# Schematic_of_device.net
KiCad netlist of a schematic drawn in Altium Designer
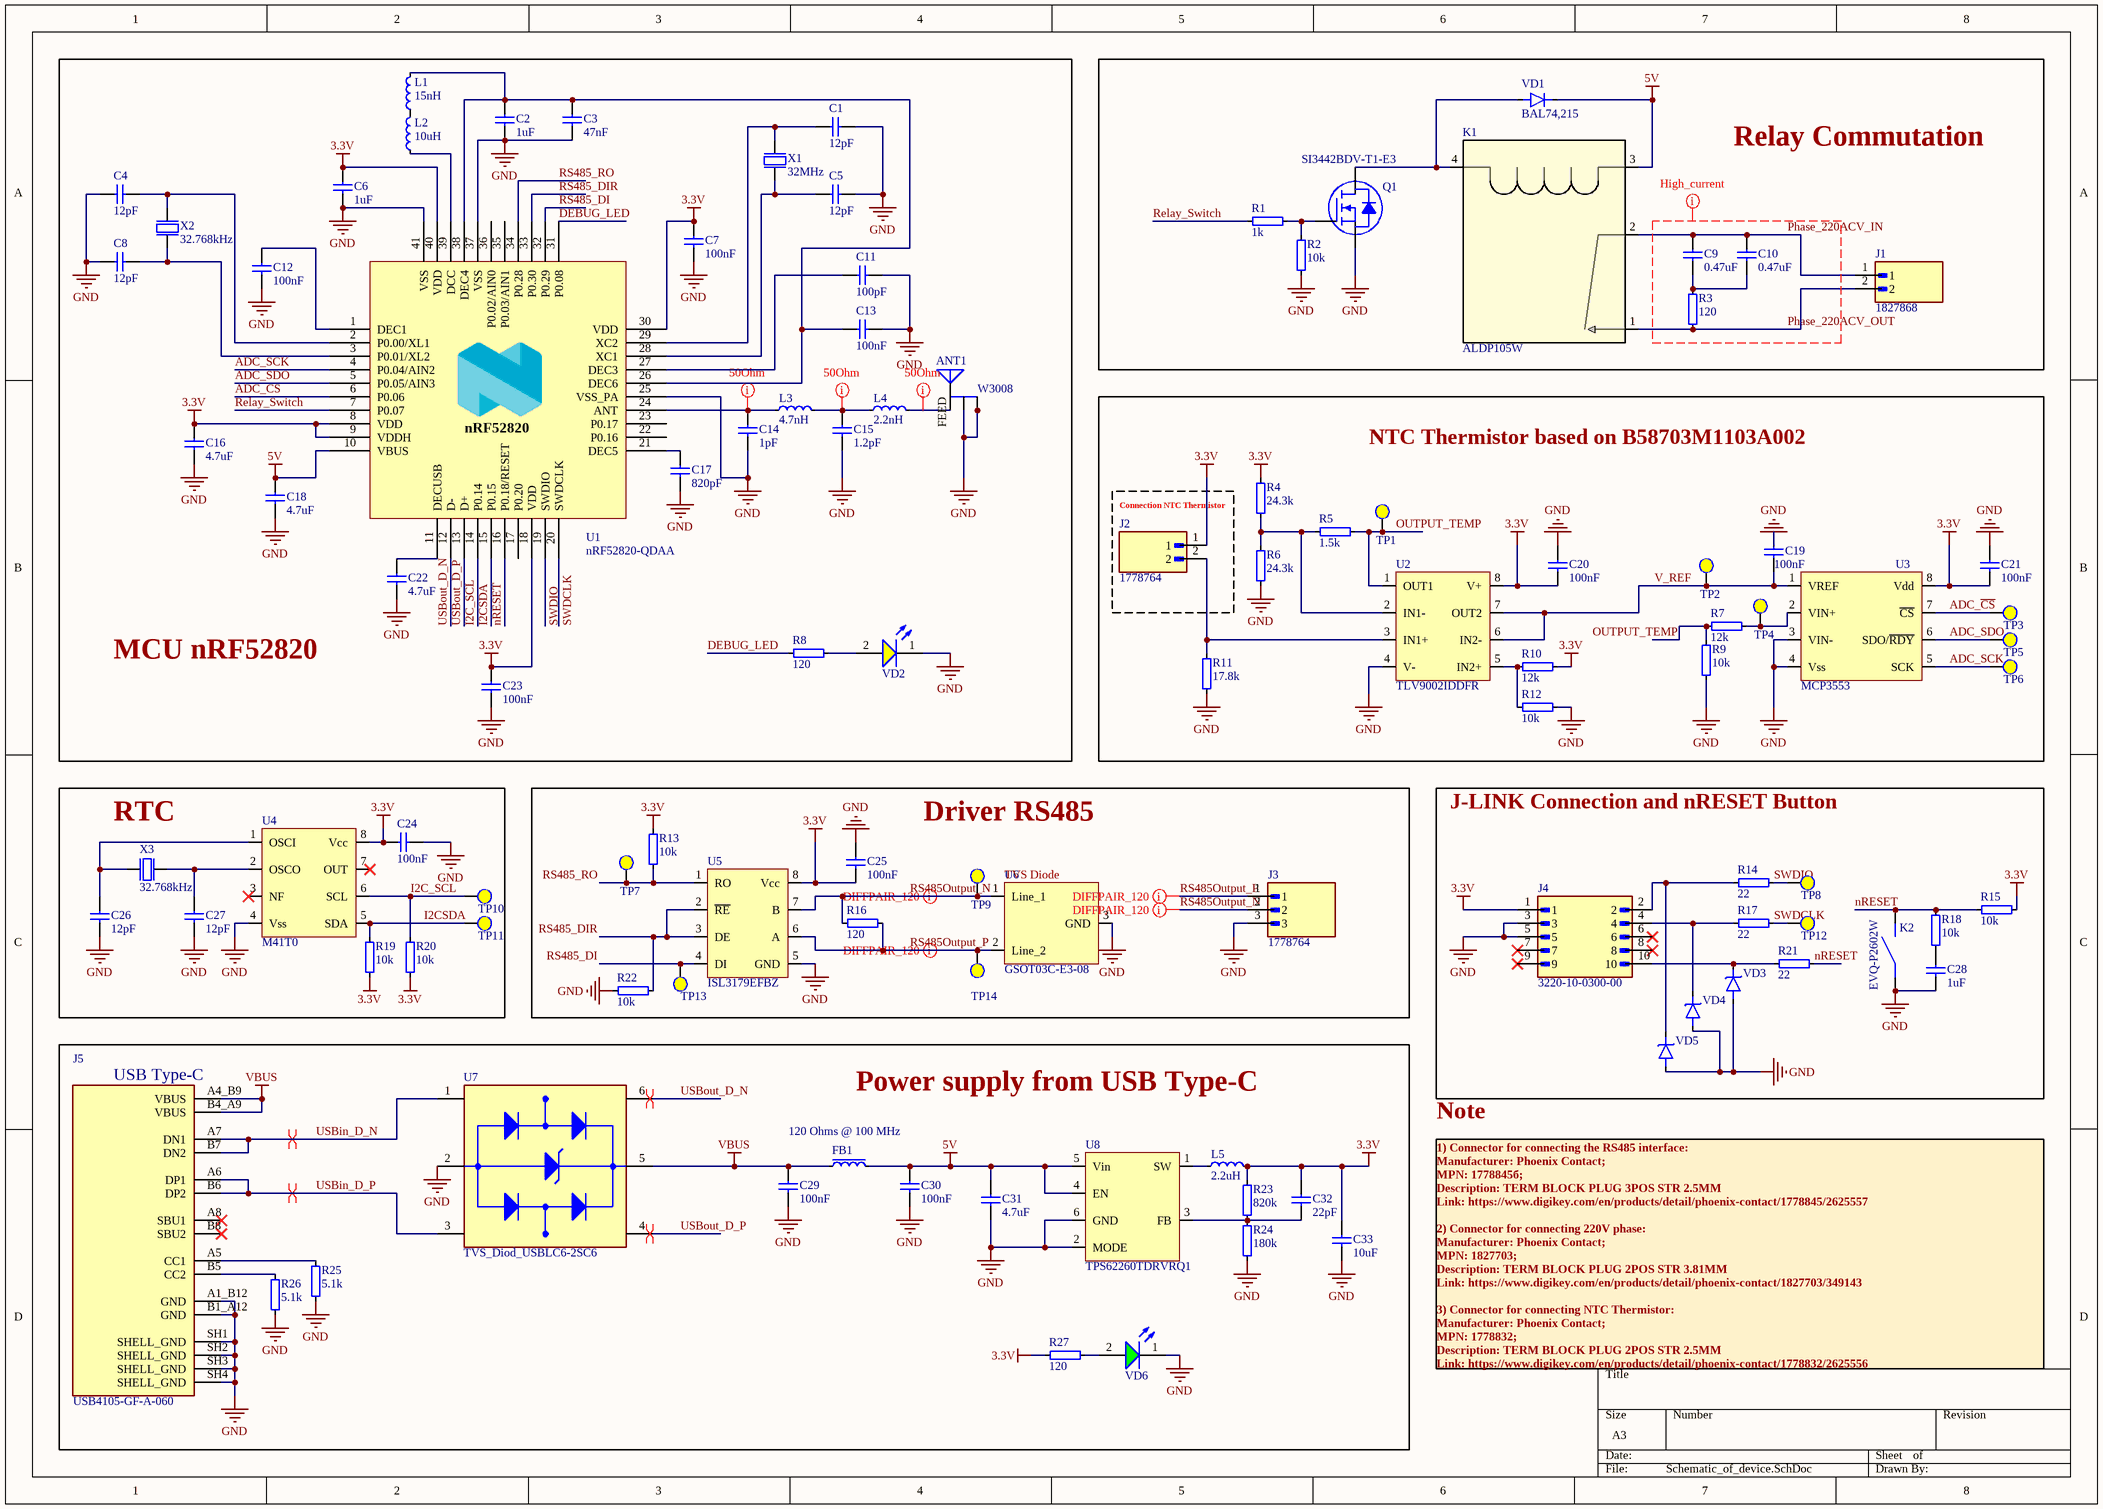
[diagram p0: Schematic_of_device.SchDoc]

(export (version "E")
  (design (tool "Eeschema 10.0.6"))
  (components
    (comp (ref "ANT1")
      (value "W3008")
      (footprint "3")
      (description "2.4GHz Bluetooth, WLAN, Zigbeeâ„¢ Chip RF Antenna 2.4GHz ~ 2.483GHz 2.2dBi Solder Surface Mount")
      (fields (field (name "MF") "PulseLarsen Antennas"))
      (libsource (lib "TT_lib") (part "W3008"))
    )
    (comp (ref "C1")
      (value "12pF")
      (footprint "C_Chip_0402")
      (description "CAP CER 12PF 200V NP0 0402")
      (fields (field (name "MANUFACTURER") "Murata Electronics") (field (name "MPN") "GQM1555C2D120FB01D"))
      (libsource (lib "TT_lib") (part "С_Chip_0402_12p"))
    )
    (comp (ref "C2")
      (value "1uF")
      (footprint "C_Chip_0402")
      (description "CAP CER 1UF 10V X7R 0402")
      (fields (field (name "MANUFACTURER") "Murata Electronics") (field (name "MPN") "GRM155Z71A105KE01J"))
      (libsource (lib "TT_lib") (part "С_Chip_0402_1u"))
    )
    (comp (ref "C3")
      (value "47nF")
      (footprint "C_Chip_0402")
      (description "CAP CER 0.047UF 50V X7R 0402")
      (fields (field (name "MANUFACTURER") "Murata Electronics") (field (name "MPN") "GRM155R71H473KE14D"))
      (libsource (lib "TT_lib") (part "С_Chip_0402_47n"))
    )
    (comp (ref "C4")
      (value "12pF")
      (footprint "C_Chip_0402")
      (description "CAP CER 12PF 200V NP0 0402")
      (fields (field (name "MANUFACTURER") "Murata Electronics") (field (name "MPN") "GQM1555C2D120FB01D"))
      (libsource (lib "TT_lib") (part "С_Chip_0402_12p"))
    )
    (comp (ref "C5")
      (value "12pF")
      (footprint "C_Chip_0402")
      (description "CAP CER 12PF 200V NP0 0402")
      (fields (field (name "MANUFACTURER") "Murata Electronics") (field (name "MPN") "GQM1555C2D120FB01D"))
      (libsource (lib "TT_lib") (part "С_Chip_0402_12p"))
    )
    (comp (ref "C6")
      (value "1uF")
      (footprint "C_Chip_0402")
      (description "CAP CER 1UF 10V X7R 0402")
      (fields (field (name "MANUFACTURER") "Murata Electronics") (field (name "MPN") "GRM155Z71A105KE01J"))
      (libsource (lib "TT_lib") (part "С_Chip_0402_1u"))
    )
    (comp (ref "C7")
      (value "100nF")
      (footprint "C_Chip_0402")
      (description "CAP CER 0.1UF 50V X7R 0402")
      (fields (field (name "MANUFACTURER") "Murata Electronics") (field (name "MPN") "GCM155R71H104KE02D"))
      (libsource (lib "TT_lib") (part "С_Chip_0402_100n"))
    )
    (comp (ref "C8")
      (value "12pF")
      (footprint "C_Chip_0402")
      (description "CAP CER 12PF 200V NP0 0402")
      (fields (field (name "MANUFACTURER") "Murata Electronics") (field (name "MPN") "GQM1555C2D120FB01D"))
      (libsource (lib "TT_lib") (part "С_Chip_0402_12p"))
    )
    (comp (ref "C9")
      (value "0.47uF")
      (footprint "C_Chip_1812")
      (description "CAP CER 0.47UF 500V X7R 1812")
      (fields
        (field (name "MANUFACTURER") "Holy Stone Enterprise Co., Ltd.")
        (field (name "MPN") "C1812X474K501T")
      )
      (libsource (lib "TT_lib") (part "С_Chip_1812_0u47"))
    )
    (comp (ref "C10")
      (value "0.47uF")
      (footprint "C_Chip_1812")
      (description "CAP CER 0.47UF 500V X7R 1812")
      (fields
        (field (name "MANUFACTURER") "Holy Stone Enterprise Co., Ltd.")
        (field (name "MPN") "C1812X474K501T")
      )
      (libsource (lib "TT_lib") (part "С_Chip_1812_0u47"))
    )
    (comp (ref "C11")
      (value "100pF")
      (footprint "C_Chip_0402")
      (description "CAP CER 100PF 50V X7R 0402")
      (fields (field (name "MANUFACTURER") "Würth Elektronik") (field (name "MPN") "885012205055"))
      (libsource (lib "TT_lib") (part "С_Chip_0402_100p"))
    )
    (comp (ref "C12")
      (value "100nF")
      (footprint "C_Chip_0402")
      (description "CAP CER 0.1UF 50V X7R 0402")
      (fields (field (name "MANUFACTURER") "Murata Electronics") (field (name "MPN") "GCM155R71H104KE02D"))
      (libsource (lib "TT_lib") (part "С_Chip_0402_100n"))
    )
    (comp (ref "C13")
      (value "100nF")
      (footprint "C_Chip_0402")
      (description "CAP CER 0.1UF 50V X7R 0402")
      (fields (field (name "MANUFACTURER") "Murata Electronics") (field (name "MPN") "GCM155R71H104KE02D"))
      (libsource (lib "TT_lib") (part "С_Chip_0402_100n"))
    )
    (comp (ref "C14")
      (value "1pF")
      (footprint "C_Chip_0402")
      (description "CAP CER 1PF 50V C0G/NP0 0402")
      (fields (field (name "MANUFACTURER") "Murata Electronics") (field (name "MPN") "GJM1555C1H1R0WB01D"))
      (libsource (lib "TT_lib") (part "С_Chip_0402_1p"))
    )
    (comp (ref "C15")
      (value "1.2pF")
      (footprint "C_Chip_0402")
      (description "CAP CER 1.2PF 50V C0G/NP0 0402")
      (fields (field (name "MANUFACTURER") "Murata Electronics") (field (name "MPN") "GRM1555C1H1R2BA01D"))
      (libsource (lib "TT_lib") (part "С_Chip_0402_1p2"))
    )
    (comp (ref "C16")
      (value "4.7uF")
      (footprint "C_Chip_0402")
      (description "CAP CER 4.7UF 16V X6T 0402")
      (fields (field (name "MANUFACTURER") "Murata Electronics") (field (name "MPN") "GRM155D81C475ME15J"))
      (libsource (lib "TT_lib") (part "С_Chip_0402_4u7"))
    )
    (comp (ref "C17")
      (value "820pF")
      (footprint "C_Chip_0402")
      (description "CAP CER 820PF 50V X7R 0402")
      (fields (field (name "MANUFACTURER") "Murata Electronics") (field (name "MPN") "GRM155R71H821KA01D"))
      (libsource (lib "TT_lib") (part "С_Chip_0402_820p"))
    )
    (comp (ref "C18")
      (value "4.7uF")
      (footprint "C_Chip_0402")
      (description "CAP CER 4.7UF 16V X6T 0402")
      (fields (field (name "MANUFACTURER") "Murata Electronics") (field (name "MPN") "GRM155D81C475ME15J"))
      (libsource (lib "TT_lib") (part "С_Chip_0402_4u7"))
    )
    (comp (ref "C19")
      (value "100nF")
      (footprint "C_Chip_0402")
      (description "CAP CER 0.1UF 50V X7R 0402")
      (fields (field (name "MANUFACTURER") "Murata Electronics") (field (name "MPN") "GCM155R71H104KE02D"))
      (libsource (lib "TT_lib") (part "С_Chip_0402_100n"))
    )
    (comp (ref "C20")
      (value "100nF")
      (footprint "C_Chip_0402")
      (description "CAP CER 0.1UF 50V X7R 0402")
      (fields (field (name "MANUFACTURER") "Murata Electronics") (field (name "MPN") "GCM155R71H104KE02D"))
      (libsource (lib "TT_lib") (part "С_Chip_0402_100n"))
    )
    (comp (ref "C21")
      (value "100nF")
      (footprint "C_Chip_0402")
      (description "CAP CER 0.1UF 50V X7R 0402")
      (fields (field (name "MANUFACTURER") "Murata Electronics") (field (name "MPN") "GCM155R71H104KE02D"))
      (libsource (lib "TT_lib") (part "С_Chip_0402_100n"))
    )
    (comp (ref "C22")
      (value "4.7uF")
      (footprint "C_Chip_0402")
      (description "CAP CER 4.7UF 16V X6T 0402")
      (fields (field (name "MANUFACTURER") "Murata Electronics") (field (name "MPN") "GRM155D81C475ME15J"))
      (libsource (lib "TT_lib") (part "С_Chip_0402_4u7"))
    )
    (comp (ref "C23")
      (value "100nF")
      (footprint "C_Chip_0402")
      (description "CAP CER 0.1UF 50V X7R 0402")
      (fields (field (name "MANUFACTURER") "Murata Electronics") (field (name "MPN") "GCM155R71H104KE02D"))
      (libsource (lib "TT_lib") (part "С_Chip_0402_100n"))
    )
    (comp (ref "C24")
      (value "100nF")
      (footprint "C_Chip_0402")
      (description "CAP CER 0.1UF 50V X7R 0402")
      (fields (field (name "MANUFACTURER") "Murata Electronics") (field (name "MPN") "GCM155R71H104KE02D"))
      (libsource (lib "TT_lib") (part "С_Chip_0402_100n"))
    )
    (comp (ref "C25")
      (value "100nF")
      (footprint "C_Chip_0402")
      (description "CAP CER 0.1UF 50V X7R 0402")
      (fields (field (name "MANUFACTURER") "Murata Electronics") (field (name "MPN") "GCM155R71H104KE02D"))
      (libsource (lib "TT_lib") (part "С_Chip_0402_100n"))
    )
    (comp (ref "C26")
      (value "12pF")
      (footprint "C_Chip_0402")
      (description "CAP CER 12PF 200V NP0 0402")
      (fields (field (name "MANUFACTURER") "Murata Electronics") (field (name "MPN") "GQM1555C2D120FB01D"))
      (libsource (lib "TT_lib") (part "С_Chip_0402_12p"))
    )
    (comp (ref "C27")
      (value "12pF")
      (footprint "C_Chip_0402")
      (description "CAP CER 12PF 200V NP0 0402")
      (fields (field (name "MANUFACTURER") "Murata Electronics") (field (name "MPN") "GQM1555C2D120FB01D"))
      (libsource (lib "TT_lib") (part "С_Chip_0402_12p"))
    )
    (comp (ref "C28")
      (value "1uF")
      (footprint "C_Chip_0402")
      (description "CAP CER 1UF 10V X7R 0402")
      (fields (field (name "MANUFACTURER") "Murata Electronics") (field (name "MPN") "GRM155Z71A105KE01J"))
      (libsource (lib "TT_lib") (part "С_Chip_0402_1u"))
    )
    (comp (ref "C29")
      (value "100nF")
      (footprint "C_Chip_0402")
      (description "CAP CER 0.1UF 50V X7R 0402")
      (fields (field (name "MANUFACTURER") "Murata Electronics") (field (name "MPN") "GCM155R71H104KE02D"))
      (libsource (lib "TT_lib") (part "С_Chip_0402_100n"))
    )
    (comp (ref "C30")
      (value "100nF")
      (footprint "C_Chip_0402")
      (description "CAP CER 0.1UF 50V X7R 0402")
      (fields (field (name "MANUFACTURER") "Murata Electronics") (field (name "MPN") "GCM155R71H104KE02D"))
      (libsource (lib "TT_lib") (part "С_Chip_0402_100n"))
    )
    (comp (ref "C31")
      (value "4.7uF")
      (footprint "C_Chip_0603")
      (description "CAP CER 4.7UF 16V X7R 0603")
      (fields (field (name "MANUFACTURER") "Murata Electronics") (field (name "MPN") "GRM188Z71C475KE21D"))
      (libsource (lib "TT_lib") (part "С_Chip_0603_4u7"))
    )
    (comp (ref "C32")
      (value "22pF")
      (footprint "C_Chip_0402")
      (description "CAP CER 22PF 16V X7R 0402")
      (fields (field (name "MANUFACTURER") "KEMET") (field (name "MPN") "C0402C220K4RAC7867"))
      (libsource (lib "TT_lib") (part "С_Chip_0402_22p"))
    )
    (comp (ref "C33")
      (value "10uF")
      (footprint "C_Chip_0603")
      (description "CAP CER 10UF 10V X7R 0603")
      (fields (field (name "MANUFACTURER") "Murata Electronics") (field (name "MPN") "GRM188Z71A106MA73D"))
      (libsource (lib "TT_lib") (part "С_Chip_0603_10u"))
    )
    (comp (ref "FB1")
      (value "120 Ohms @ 100 MHz")
      (footprint "Ferrite_Bead_0402")
      (description "FERRITE BEAD 120 OHM 0402 1LN")
      (fields
        (field (name "MANUFACTURER") "Laird-Signal Integrity Products")
        (field (name "MPN") "LI0402D121R-10")
      )
      (libsource (lib "TT_lib") (part "Ferrite_Beads"))
    )
    (comp (ref "J1")
      (value "1827868")
      (footprint "Phoenix_1827868")
      (description "TERM BLOCK HDR 2POS 90DEG 3.81MM")
      (fields (field (name "MANUFACTURER") "Phoenix Contact"))
      (libsource (lib "TT_lib") (part "Phoenix_2pin_male"))
    )
    (comp (ref "J2")
      (value "1778764")
      (footprint "PHoenix_1778764")
      (description "TERM BLOCK HDR 2POS 90DEG 2.5MM")
      (fields (field (name "MANUFACTURER") "Phoenix Contact"))
      (libsource (lib "TT_lib") (part "Male_2_Position_Terminal_Block_Header"))
    )
    (comp (ref "J3")
      (value "1778764")
      (footprint "Phoenix_1778777")
      (description "TERM BLOCK HDR 3POS 90DEG 2.5MM")
      (fields (field (name "MANUFACTURER") "Phoenix Contact") (field (name "MPN") "1778777"))
      (libsource (lib "TT_lib") (part "Male_3_Position_Terminal_Block_Header"))
    )
    (comp (ref "J4")
      (value "3220-10-0300-00")
      (footprint "CNC_TECH_")
      (description "CONN HEADER SMD 10POS 1.27MM")
      (fields (field (name "MANUFACTURER") "CNC Tech"))
      (libsource (lib "TT_lib") (part "3220-10-0300-00"))
    )
    (comp (ref "J5")
      (value "USB4105-GF-A-060")
      (footprint "USB_TypeC_FP")
      (description "CONN RCP USB2.0 TYP C 24P SMD RA")
      (fields (field (name "MANUFACTURER") "GCT"))
      (libsource (lib "TT_lib") (part "USB_TypeC"))
    )
    (comp (ref "K1")
      (value "ALDP105W")
      (footprint "Rekay")
      (description "RELAY GEN PURPOSE SPST 5A 5V")
      (fields (field (name "MANUFACTURER") "Panasonic Electric Works"))
      (libsource (lib "TT_lib") (part "Relay"))
    )
    (comp (ref "K2")
      (value "EVQ-P2602W")
      (footprint "Button")
      (description "SWITCH TACTILE SPST-NO 0.02A 15V")
      (fields (field (name "MANUFACTURER") "Panasonic Electronic Components"))
      (libsource (lib "TT_lib") (part "Button"))
    )
    (comp (ref "L1")
      (value "15nH")
      (footprint "L_Chip_0402")
      (description "FIXED IND 15NH 250MA 600MOHM SMD")
      (fields
        (field (name "MANUFACTURER") "Johanson Technology Inc.")
        (field (name "MPN") "LRC0402CJ15NGV001T")
      )
      (libsource (lib "TT_lib") (part "L_Chip_0402_15n"))
    )
    (comp (ref "L2")
      (value "10uH")
      (footprint "L_Chip_0402")
      (description "FIXED IND 10UH 380MA 468MOHM SMD")
      (fields (field (name "MANUFACTURER") "Taiyo Yuden") (field (name "MPN") "CBMF1608T100K"))
      (libsource (lib "TT_lib") (part "L_Chip_0402_10u"))
    )
    (comp (ref "L3")
      (value "4.7nH")
      (footprint "L_Chip_0402")
      (description "FIXED IND 4.7NH 700MA 0.16OHM SM")
      (fields (field (name "MANUFACTURER") "Murata Electronics") (field (name "MPN") "LQG15HS4N7S02D"))
      (libsource (lib "TT_lib") (part "L_Chip_0402_4n7"))
    )
    (comp (ref "L4")
      (value "2.2nH")
      (footprint "L_Chip_0402")
      (description "FIXED IND 2.2NH 900MA 150MOHM SM")
      (fields (field (name "MANUFACTURER") "TDK Corporation") (field (name "MPN") "MLG1005S2N2BT000"))
      (libsource (lib "TT_lib") (part "L_Chip_0402_2n2"))
    )
    (comp (ref "L5")
      (value "2.2uH")
      (footprint "L_Chip_1008")
      (description "FIXED IND 2.2UH 1A 150 MOHM SMD")
      (fields (field (name "MANUFACTURER") "Murata Electronics") (field (name "MPN") "LQM2HPN2R2MJ0L"))
      (libsource (lib "TT_lib") (part "L_Chip_1008_2u2"))
    )
    (comp (ref "Q1")
      (value "SI3442BDV-T1-E3")
      (footprint "TSOP-6")
      (description "MOSFET N-CH 20V 3A 6TSOP")
      (fields (field (name "MANUFACTURER") "Vishay Siliconix"))
      (libsource (lib "TT_lib") (part "N-chenal_MOSFET"))
    )
    (comp (ref "R1")
      (value "1k")
      (footprint "R_Chip_0402")
      (description "RES 1K OHM 1% 1/8W 0402")
      (fields (field (name "MANUFACTURER") "YAGEO") (field (name "MPN") "AC0402FR-7W1KL"))
      (libsource (lib "TT_lib") (part "R_Chip_0402_1k"))
    )
    (comp (ref "R2")
      (value "10k")
      (footprint "R_Chip_0402")
      (description "RES 10K OHM 1% 1/8W 0402")
      (fields
        (field (name "MANUFACTURER") "TE Connectivity Passive Product")
        (field (name "MPN") "CRGP0402F10K")
      )
      (libsource (lib "TT_lib") (part "R_Chip_0402_10k"))
    )
    (comp (ref "R3")
      (value "120")
      (footprint "R_Chip_1210")
      (description "RES 120 OHM 1% 1W 1210")
      (fields (field (name "MANUFACTURER") "YAGEO") (field (name "MPN") "AC1210FR-7W120RL"))
      (libsource (lib "TT_lib") (part "R_Chip_1210_120"))
    )
    (comp (ref "R4")
      (value "24.3k")
      (footprint "R_Chip_0402")
      (description "RES 24.3K OHM 1% 1/8W 0402")
      (fields (field (name "MANUFACTURER") "YAGEO") (field (name "MPN") "AC0402FR-7W24K3L"))
      (libsource (lib "TT_lib") (part "R_Chip_0402_24k3"))
    )
    (comp (ref "R5")
      (value "1.5k")
      (footprint "R_Chip_0402")
      (description "RES 1.5K OHM 1% 1/8W 0402")
      (fields
        (field (name "MANUFACTURER") "TE Connectivity Passive Product")
        (field (name "MPN") "CRGP0402F1K5")
      )
      (libsource (lib "TT_lib") (part "R_Chip_0402_1k5"))
    )
    (comp (ref "R6")
      (value "24.3k")
      (footprint "R_Chip_0402")
      (description "RES 24.3K OHM 1% 1/8W 0402")
      (fields (field (name "MANUFACTURER") "YAGEO") (field (name "MPN") "AC0402FR-7W24K3L"))
      (libsource (lib "TT_lib") (part "R_Chip_0402_24k3"))
    )
    (comp (ref "R7")
      (value "12k")
      (footprint "R_Chip_0402")
      (description "RES 12K OHM 1% 1/8W 0402")
      (fields
        (field (name "MANUFACTURER") "TE Connectivity Passive Product")
        (field (name "MPN") "CRGP0402F12K")
      )
      (libsource (lib "TT_lib") (part "R_Chip_0402_12k"))
    )
    (comp (ref "R8")
      (value "120")
      (footprint "R_Chip_0402")
      (description "RES 120 OHM 1% 1/8W 0402")
      (fields
        (field (name "MANUFACTURER") "TE Connectivity Passive Product")
        (field (name "MPN") "CRGP0402F120R")
      )
      (libsource (lib "TT_lib") (part "R_Chip_0402_120"))
    )
    (comp (ref "R9")
      (value "10k")
      (footprint "R_Chip_0402")
      (description "RES 10K OHM 1% 1/8W 0402")
      (fields
        (field (name "MANUFACTURER") "TE Connectivity Passive Product")
        (field (name "MPN") "CRGP0402F10K")
      )
      (libsource (lib "TT_lib") (part "R_Chip_0402_10k"))
    )
    (comp (ref "R10")
      (value "12k")
      (footprint "R_Chip_0402")
      (description "RES 12K OHM 1% 1/8W 0402")
      (fields
        (field (name "MANUFACTURER") "TE Connectivity Passive Product")
        (field (name "MPN") "CRGP0402F12K")
      )
      (libsource (lib "TT_lib") (part "R_Chip_0402_12k"))
    )
    (comp (ref "R11")
      (value "17.8k")
      (footprint "R_Chip_0402")
      (description "RES SMD 17.8K OHM 1% 1/10W 0402")
      (fields
        (field (name "MANUFACTURER") "Panasonic Electronic Components")
        (field (name "MPN") "ERJ-2RKF1782X")
      )
      (libsource (lib "TT_lib") (part "R_Chip_0402_17k8"))
    )
    (comp (ref "R12")
      (value "10k")
      (footprint "R_Chip_0402")
      (description "RES 10K OHM 1% 1/8W 0402")
      (fields
        (field (name "MANUFACTURER") "TE Connectivity Passive Product")
        (field (name "MPN") "CRGP0402F10K")
      )
      (libsource (lib "TT_lib") (part "R_Chip_0402_10k"))
    )
    (comp (ref "R13")
      (value "10k")
      (footprint "R_Chip_0402")
      (description "RES 10K OHM 1% 1/8W 0402")
      (fields
        (field (name "MANUFACTURER") "TE Connectivity Passive Product")
        (field (name "MPN") "CRGP0402F10K")
      )
      (libsource (lib "TT_lib") (part "R_Chip_0402_10k"))
    )
    (comp (ref "R14")
      (value "22")
      (footprint "R_Chip_0402")
      (description "RES SMD 22 OHM 1% 1/10W 0402")
      (fields
        (field (name "MANUFACTURER") "Panasonic Electronic Components")
        (field (name "MPN") "ERJ-2RKF22R0X")
      )
      (libsource (lib "TT_lib") (part "R_Chip_0402_22"))
    )
    (comp (ref "R15")
      (value "10k")
      (footprint "R_Chip_0402")
      (description "RES 10K OHM 1% 1/8W 0402")
      (fields
        (field (name "MANUFACTURER") "TE Connectivity Passive Product")
        (field (name "MPN") "CRGP0402F10K")
      )
      (libsource (lib "TT_lib") (part "R_Chip_0402_10k"))
    )
    (comp (ref "R16")
      (value "120")
      (footprint "R_Chip_0402")
      (description "RES 120 OHM 1% 1/8W 0402")
      (fields
        (field (name "MANUFACTURER") "TE Connectivity Passive Product")
        (field (name "MPN") "CRGP0402F120R")
      )
      (libsource (lib "TT_lib") (part "R_Chip_0402_120"))
    )
    (comp (ref "R17")
      (value "22")
      (footprint "R_Chip_0402")
      (description "RES SMD 22 OHM 1% 1/10W 0402")
      (fields
        (field (name "MANUFACTURER") "Panasonic Electronic Components")
        (field (name "MPN") "ERJ-2RKF22R0X")
      )
      (libsource (lib "TT_lib") (part "R_Chip_0402_22"))
    )
    (comp (ref "R18")
      (value "10k")
      (footprint "R_Chip_0402")
      (description "RES 10K OHM 1% 1/8W 0402")
      (fields
        (field (name "MANUFACTURER") "TE Connectivity Passive Product")
        (field (name "MPN") "CRGP0402F10K")
      )
      (libsource (lib "TT_lib") (part "R_Chip_0402_10k"))
    )
    (comp (ref "R19")
      (value "10k")
      (footprint "R_Chip_0402")
      (description "RES 10K OHM 1% 1/8W 0402")
      (fields
        (field (name "MANUFACTURER") "TE Connectivity Passive Product")
        (field (name "MPN") "CRGP0402F10K")
      )
      (libsource (lib "TT_lib") (part "R_Chip_0402_10k"))
    )
    (comp (ref "R20")
      (value "10k")
      (footprint "R_Chip_0402")
      (description "RES 10K OHM 1% 1/8W 0402")
      (fields
        (field (name "MANUFACTURER") "TE Connectivity Passive Product")
        (field (name "MPN") "CRGP0402F10K")
      )
      (libsource (lib "TT_lib") (part "R_Chip_0402_10k"))
    )
    (comp (ref "R21")
      (value "22")
      (footprint "R_Chip_0402")
      (description "RES SMD 22 OHM 1% 1/10W 0402")
      (fields
        (field (name "MANUFACTURER") "Panasonic Electronic Components")
        (field (name "MPN") "ERJ-2RKF22R0X")
      )
      (libsource (lib "TT_lib") (part "R_Chip_0402_22"))
    )
    (comp (ref "R22")
      (value "10k")
      (footprint "R_Chip_0402")
      (description "RES 10K OHM 1% 1/8W 0402")
      (fields
        (field (name "MANUFACTURER") "TE Connectivity Passive Product")
        (field (name "MPN") "CRGP0402F10K")
      )
      (libsource (lib "TT_lib") (part "R_Chip_0402_10k"))
    )
    (comp (ref "R23")
      (value "820k")
      (footprint "R_Chip_0402")
      (description "RES 820K OHM 1% 1/4W 0402")
      (fields
        (field (name "MANUFACTURER") "Panasonic Electronic Components")
        (field (name "MPN") "ERJ-PA2F8203X")
      )
      (libsource (lib "TT_lib") (part "R_Chip_0402_820k"))
    )
    (comp (ref "R24")
      (value "180k")
      (footprint "R_Chip_0402")
      (description "RES 180K OHM 1% 1/4W 0402")
      (fields
        (field (name "MANUFACTURER") "Panasonic Electronic Components")
        (field (name "MPN") "ERJ-PA2F1803X")
      )
      (libsource (lib "TT_lib") (part "R_Chip_0402_180k"))
    )
    (comp (ref "R25")
      (value "5.1k")
      (footprint "R_Chip_0402")
      (description "RES 5.1K OHM 1% 1/8W 0402")
      (fields (field (name "MANUFACTURER") "YAGEO") (field (name "MPN") "RC0402FR-7W5K1L"))
      (libsource (lib "TT_lib") (part "R_Chip_0402_5k1"))
    )
    (comp (ref "R26")
      (value "5.1k")
      (footprint "R_Chip_0402")
      (description "RES 5.1K OHM 1% 1/8W 0402")
      (fields (field (name "MANUFACTURER") "YAGEO") (field (name "MPN") "RC0402FR-7W5K1L"))
      (libsource (lib "TT_lib") (part "R_Chip_0402_5k1"))
    )
    (comp (ref "R27")
      (value "120")
      (footprint "R_Chip_0402")
      (description "RES 120 OHM 1% 1/8W 0402")
      (fields
        (field (name "MANUFACTURER") "TE Connectivity Passive Product")
        (field (name "MPN") "CRGP0402F120R")
      )
      (libsource (lib "TT_lib") (part "R_Chip_0402_120"))
    )
    (comp (ref "TP1")
      (value "test point")
      (footprint "Test_Point")
      (libsource (lib "TT_lib") (part "Test_Point"))
    )
    (comp (ref "TP2")
      (value "test point")
      (footprint "Test_Point")
      (libsource (lib "TT_lib") (part "Test_Point"))
    )
    (comp (ref "TP3")
      (value "test point")
      (footprint "Test_Point")
      (libsource (lib "TT_lib") (part "Test_Point"))
    )
    (comp (ref "TP4")
      (value "test point")
      (footprint "Test_Point")
      (libsource (lib "TT_lib") (part "Test_Point"))
    )
    (comp (ref "TP5")
      (value "test point")
      (footprint "Test_Point")
      (libsource (lib "TT_lib") (part "Test_Point"))
    )
    (comp (ref "TP6")
      (value "test point")
      (footprint "Test_Point")
      (libsource (lib "TT_lib") (part "Test_Point"))
    )
    (comp (ref "TP7")
      (value "test point")
      (footprint "Test_Point")
      (libsource (lib "TT_lib") (part "Test_Point"))
    )
    (comp (ref "TP8")
      (value "test point")
      (footprint "Test_Point")
      (libsource (lib "TT_lib") (part "Test_Point"))
    )
    (comp (ref "TP9")
      (value "test point")
      (footprint "Test_Point")
      (libsource (lib "TT_lib") (part "Test_Point"))
    )
    (comp (ref "TP10")
      (value "test point")
      (footprint "Test_Point")
      (libsource (lib "TT_lib") (part "Test_Point"))
    )
    (comp (ref "TP11")
      (value "test point")
      (footprint "Test_Point")
      (libsource (lib "TT_lib") (part "Test_Point"))
    )
    (comp (ref "TP12")
      (value "test point")
      (footprint "Test_Point")
      (libsource (lib "TT_lib") (part "Test_Point"))
    )
    (comp (ref "TP13")
      (value "test point")
      (footprint "Test_Point")
      (libsource (lib "TT_lib") (part "Test_Point"))
    )
    (comp (ref "TP14")
      (value "test point")
      (footprint "Test_Point")
      (libsource (lib "TT_lib") (part "Test_Point"))
    )
    (comp (ref "U1")
      (value "nRF52820-QDAA")
      (footprint "QFN40P500X500X50_HS-41N")
      (description "Multi-protocol Bluetooth Low Energy, IEEE 802.15.4, ANT and 2.4GHz proprietary system-on-chip")
      (fields (field (name "MANUFACTURER") "?") (field (name "PUBLISHER") "Nordic Semiconductor"))
      (libsource (lib "TT_lib") (part "nRF52820-QDAA"))
    )
    (comp (ref "U2")
      (value "TLV9002IDDFR")
      (footprint "SOT23-8")
      (fields (field (name "MANUFACTURER") "Texas Instruments"))
      (libsource (lib "TT_lib") (part "OP_AMP_TLV9002IDDFR"))
    )
    (comp (ref "U3")
      (value "MCP3553")
      (footprint "SOP8")
      (description "IC ADC 22BIT SIGMA-DELTA 8MSOP")
      (fields (field (name "MPN") "MCP3553T-E/MS"))
      (libsource (lib "TT_lib") (part "ADC_MCP3553"))
    )
    (comp (ref "U4")
      (value "M41T0")
      (footprint "8-SOIC")
      (description "IC RTC CLK/CALENDAR I2C 8SOIC")
      (fields (field (name "MPN") "M41T0M6F"))
      (libsource (lib "TT_lib") (part "RTC_M41T0"))
    )
    (comp (ref "U5")
      (value "ISL3179EFBZ")
      (footprint "8-SOIC")
      (description "IC TRANSCEIVER HALF 1/1 8SOIC")
      (libsource (lib "TT_lib") (part "RS485_ISL3179EFBZ"))
    )
    (comp (ref "U6")
      (value "GSOT03C-E3-08")
      (footprint "SOT23-3")
      (description "TVS DIODE 3.3VWM 12.3VC SOT23-3")
      (fields (field (name "MANUFACTURER") "Vishay General Semiconductor - Diodes Division"))
      (libsource (lib "TT_lib") (part "TVS_D_GSOT03C-E3-08"))
    )
    (comp (ref "U7")
      (value "TVS_Diod_USBLC6-2SC6")
      (footprint "SOT95P280X145-6N")
      (description "17V Clamp 5A (8/20Âµs) Ipp Tvs Diode Surface Mount SOT-23-6")
      (fields (field (name "MF") "STMicroelectronics") (field (name "MP") "USBLC6-2SC6"))
      (libsource (lib "TT_lib") (part "TVS_Diod_USBLC6-2SC6"))
    )
    (comp (ref "U8")
      (value "TPS62260TDRVRQ1")
      (footprint "SON7P65_200X200X80L25X30T160X100N")
      (description "IC REG BUCK ADJ 600MA 6WSON")
      (fields (field (name "MANUFACTURER") "Texas Instruments"))
      (libsource (lib "TT_lib") (part "TPS62260TDRVRQ1"))
    )
    (comp (ref "VD1")
      (value "BAL74,215")
      (footprint "SOT23-3")
      (description "DIODE GEN PURP 50V 215MA TO236AB")
      (fields (field (name "MANUFACTURER") "Nexperia USA Inc."))
      (libsource (lib "TT_lib") (part "D_BAL74_215"))
    )
    (comp (ref "VD2")
      (value "Yellow, 2V, 140°")
      (footprint "WL-SMCW_0603_150060xx75003")
      (description "WL-SMCW Mono-color Chip LED Waterclear, size 0603, Yellow, 2V, 140°")
      (fields
        (field (name "MANUFACTURER PART NUMBER") "150060YS75000")
        (field (name "MANUFACTURER") "Wurth Elektronik")
      )
      (libsource (lib "TT_lib") (part "150060YS75000"))
    )
    (comp (ref "VD3")
      (value "SP3205-01ETG")
      (footprint "SP320501ETG")
      (description "TVS DIODE 3.3VWM 12VC SOD882")
      (fields (field (name "MANUFACTURER") "Littelfuse Inc."))
      (libsource (lib "TT_lib") (part "TVS_diode_1chenal"))
    )
    (comp (ref "VD4")
      (value "SP3205-01ETG")
      (footprint "SP320501ETG")
      (description "TVS DIODE 3.3VWM 12VC SOD882")
      (fields (field (name "MANUFACTURER") "Littelfuse Inc."))
      (libsource (lib "TT_lib") (part "TVS_diode_1chenal"))
    )
    (comp (ref "VD5")
      (value "SP3205-01ETG")
      (footprint "SP320501ETG")
      (description "TVS DIODE 3.3VWM 12VC SOD882")
      (fields (field (name "MANUFACTURER") "Littelfuse Inc."))
      (libsource (lib "TT_lib") (part "TVS_diode_1chenal"))
    )
    (comp (ref "VD6")
      (value "Bright Green, 2V, 60°")
      (footprint "WL-SMCW_0603_150060xx75003")
      (description "WL-SMCW Mono-color Chip LED Waterclear, size 0603, Bright Green, 2V, 60°")
      (fields
        (field (name "MANUFACTURER PART NUMBER") "150060VS86000")
        (field (name "MANUFACTURER") "Wurth Elektronik")
      )
      (libsource (lib "TT_lib") (part "150060VS86000"))
    )
    (comp (ref "X1")
      (value "32MHz")
      (footprint "Osc_32MHz")
      (fields
        (field (name "MANUFACTURER") "Suntsu Electronics, Inc")
        (field (name "MPN") "SXT3248AA48-32.000M")
        (field (name "TOLERANCE") "?")
      )
      (libsource (lib "TT_lib") (part "X_Crystal_32MHz"))
    )
    (comp (ref "X2")
      (value "32.768kHz")
      (footprint "Osc_32_768kHz")
      (fields
        (field (name "MANUFACTURER") "Raltron Electronics")
        (field (name "MPN") "RT2012-32.768-9-TR")
        (field (name "TOLERANCE") "?")
      )
      (libsource (lib "TT_lib") (part "X_Crystal_32_768kHz"))
    )
    (comp (ref "X3")
      (value "32.768kHz")
      (footprint "Osc_32_768kHz")
      (fields
        (field (name "MANUFACTURER") "Raltron Electronics")
        (field (name "MPN") "RT2012-32.768-9-TR")
        (field (name "TOLERANCE") "?")
      )
      (libsource (lib "TT_lib") (part "X_Crystal_32_768kHz"))
    )
  )
  (nets
    (net (code "1") (name "/ADC_SCK") (class "Default")
      (node (ref "TP6") (pin "1") (pinfunction "1_1") (pintype "passive"))
      (node (ref "U1") (pin "4") (pinfunction "P0.04/AIN2_4") (pintype "passive"))
      (node (ref "U3") (pin "5") (pinfunction "SCK_5") (pintype "passive"))
    )
    (net (code "2") (name "/ADC_SDO") (class "Default")
      (node (ref "TP5") (pin "1") (pinfunction "1_1") (pintype "passive"))
      (node (ref "U1") (pin "5") (pinfunction "P0.05/AIN3_5") (pintype "passive"))
      (node (ref "U3") (pin "6") (pinfunction "SDO/~{RDY}_6") (pintype "passive"))
    )
    (net (code "3") (name "/ADC_~{CS}") (class "Default")
      (node (ref "TP3") (pin "1") (pinfunction "1_1") (pintype "passive"))
      (node (ref "U1") (pin "6") (pinfunction "P0.06_6") (pintype "passive"))
      (node (ref "U3") (pin "7") (pinfunction "~{CS}_7") (pintype "passive"))
    )
    (net (code "4") (name "/DEBUG_LED") (class "Default")
      (node (ref "R8") (pin "1") (pinfunction "1_1") (pintype "passive"))
      (node (ref "U1") (pin "31") (pinfunction "P0.08_31") (pintype "passive"))
    )
    (net (code "5") (name "/I2CSDA") (class "Default")
      (node (ref "R19") (pin "2") (pinfunction "2_2") (pintype "passive"))
      (node (ref "TP11") (pin "1") (pinfunction "1_1") (pintype "passive"))
      (node (ref "U1") (pin "15") (pinfunction "P0.15_15") (pintype "passive"))
      (node (ref "U4") (pin "5") (pinfunction "SDA_5") (pintype "passive"))
    )
    (net (code "6") (name "/I2C_SCL") (class "Default")
      (node (ref "R20") (pin "2") (pinfunction "2_2") (pintype "passive"))
      (node (ref "TP10") (pin "1") (pinfunction "1_1") (pintype "passive"))
      (node (ref "U1") (pin "14") (pinfunction "P0.14_14") (pintype "passive"))
      (node (ref "U4") (pin "6") (pinfunction "SCL_6") (pintype "passive"))
    )
    (net (code "7") (name "/OUTPUT_TEMP") (class "Default")
      (node (ref "R5") (pin "2") (pinfunction "2_2") (pintype "passive"))
      (node (ref "R7") (pin "1") (pinfunction "1_1") (pintype "passive"))
      (node (ref "R9") (pin "2") (pinfunction "2_2") (pintype "passive"))
      (node (ref "TP1") (pin "1") (pinfunction "1_1") (pintype "passive"))
      (node (ref "U2") (pin "1") (pinfunction "OUT1_1") (pintype "passive"))
    )
    (net (code "8") (name "/Phase_220ACV_IN") (class "Default")
      (node (ref "C10") (pin "2") (pinfunction "2_2") (pintype "passive"))
      (node (ref "C9") (pin "2") (pinfunction "2_2") (pintype "passive"))
      (node (ref "J1") (pin "1") (pinfunction "1_1") (pintype "passive"))
      (node (ref "K1") (pin "2") (pinfunction "2_2") (pintype "passive"))
    )
    (net (code "9") (name "/Phase_220ACV_OUT") (class "Default")
      (node (ref "J1") (pin "2") (pinfunction "2_2") (pintype "passive"))
      (node (ref "K1") (pin "1") (pinfunction "1_1") (pintype "passive"))
      (node (ref "R3") (pin "1") (pinfunction "1_1") (pintype "passive"))
    )
    (net (code "10") (name "/RS485Output_N") (class "Default")
      (node (ref "J3") (pin "2") (pinfunction "2_2") (pintype "passive"))
      (node (ref "R16") (pin "1") (pinfunction "1_1") (pintype "passive"))
      (node (ref "TP9") (pin "1") (pinfunction "1_1") (pintype "passive"))
      (node (ref "U5") (pin "7") (pinfunction "B_7") (pintype "passive"))
      (node (ref "U6") (pin "1") (pinfunction "Line_1_1") (pintype "passive"))
    )
    (net (code "11") (name "/RS485Output_P") (class "Default")
      (node (ref "J3") (pin "1") (pinfunction "1_1") (pintype "passive"))
      (node (ref "R16") (pin "2") (pinfunction "2_2") (pintype "passive"))
      (node (ref "TP14") (pin "1") (pinfunction "1_1") (pintype "passive"))
      (node (ref "U5") (pin "6") (pinfunction "A_6") (pintype "passive"))
      (node (ref "U6") (pin "2") (pinfunction "Line_2_2") (pintype "passive"))
    )
    (net (code "12") (name "/RS485_DI") (class "Default")
      (node (ref "TP13") (pin "1") (pinfunction "1_1") (pintype "passive"))
      (node (ref "U1") (pin "32") (pinfunction "P0.29_32") (pintype "passive"))
      (node (ref "U5") (pin "4") (pinfunction "DI_4") (pintype "passive"))
    )
    (net (code "13") (name "/RS485_DIR") (class "Default")
      (node (ref "R22") (pin "2") (pinfunction "2_2") (pintype "passive"))
      (node (ref "U1") (pin "33") (pinfunction "P0.30_33") (pintype "passive"))
      (node (ref "U5") (pin "2") (pinfunction "~{RE}_2") (pintype "passive"))
      (node (ref "U5") (pin "3") (pinfunction "DE_3") (pintype "passive"))
    )
    (net (code "14") (name "/RS485_RO") (class "Default")
      (node (ref "R13") (pin "1") (pinfunction "1_1") (pintype "passive"))
      (node (ref "TP7") (pin "1") (pinfunction "1_1") (pintype "passive"))
      (node (ref "U1") (pin "34") (pinfunction "P0.28_34") (pintype "passive"))
      (node (ref "U5") (pin "1") (pinfunction "RO_1") (pintype "passive"))
    )
    (net (code "15") (name "/Relay_Switch") (class "Default")
      (node (ref "R1") (pin "1") (pinfunction "1_1") (pintype "passive"))
      (node (ref "U1") (pin "7") (pinfunction "P0.07_7") (pintype "passive"))
    )
    (net (code "16") (name "/SWDCLK") (class "Default")
      (node (ref "R17") (pin "2") (pinfunction "2_2") (pintype "passive"))
      (node (ref "TP12") (pin "1") (pinfunction "1_1") (pintype "passive"))
      (node (ref "U1") (pin "20") (pinfunction "SWDCLK_20") (pintype "passive"))
    )
    (net (code "17") (name "/SWDIO") (class "Default")
      (node (ref "R14") (pin "2") (pinfunction "2_2") (pintype "passive"))
      (node (ref "TP8") (pin "1") (pinfunction "1_1") (pintype "passive"))
      (node (ref "U1") (pin "19") (pinfunction "SWDIO_19") (pintype "passive"))
    )
    (net (code "18") (name "/USBin_D_N") (class "Default")
      (node (ref "J5") (pin "A7") (pinfunction "DN1_A7") (pintype "passive"))
      (node (ref "J5") (pin "B7") (pinfunction "DN2_B7") (pintype "passive"))
      (node (ref "U7") (pin "1") (pinfunction "I/O1_IN_1") (pintype "passive"))
    )
    (net (code "19") (name "/USBin_D_P") (class "Default")
      (node (ref "J5") (pin "A6") (pinfunction "DP1_A6") (pintype "passive"))
      (node (ref "J5") (pin "B6") (pinfunction "DP2_B6") (pintype "passive"))
      (node (ref "U7") (pin "3") (pinfunction "I/O2_IN_3") (pintype "passive"))
    )
    (net (code "20") (name "/USBout_D_N") (class "Default")
      (node (ref "U1") (pin "12") (pinfunction "D-_12") (pintype "passive"))
      (node (ref "U7") (pin "6") (pinfunction "I/O1_OUT_6") (pintype "passive"))
    )
    (net (code "21") (name "/USBout_D_P") (class "Default")
      (node (ref "U1") (pin "13") (pinfunction "D+_13") (pintype "passive"))
      (node (ref "U7") (pin "4") (pinfunction "I/O2_OUT_4") (pintype "passive"))
    )
    (net (code "22") (name "/V_REF") (class "Default")
      (node (ref "C19") (pin "1") (pinfunction "1_1") (pintype "passive"))
      (node (ref "TP2") (pin "1") (pinfunction "1_1") (pintype "passive"))
      (node (ref "U2") (pin "6") (pinfunction "IN2-_6") (pintype "passive"))
      (node (ref "U2") (pin "7") (pinfunction "OUT2_7") (pintype "passive"))
      (node (ref "U3") (pin "1") (pinfunction "VREF_1") (pintype "passive"))
    )
    (net (code "23") (name "/nRESET") (class "Default")
      (node (ref "K2") (pin "4") (pinfunction "4_4") (pintype "passive"))
      (node (ref "R15") (pin "1") (pinfunction "1_1") (pintype "passive"))
      (node (ref "R18") (pin "1") (pinfunction "1_1") (pintype "passive"))
      (node (ref "R21") (pin "2") (pinfunction "2_2") (pintype "passive"))
      (node (ref "U1") (pin "16") (pinfunction "P0.18/RESET_16") (pintype "passive"))
    )
    (net (code "24") (name "3.3V") (class "Default")
      (node (ref "C16") (pin "2") (pinfunction "2_2") (pintype "passive"))
      (node (ref "C20") (pin "2") (pinfunction "2_2") (pintype "passive"))
      (node (ref "C21") (pin "2") (pinfunction "2_2") (pintype "passive"))
      (node (ref "C23") (pin "2") (pinfunction "2_2") (pintype "passive"))
      (node (ref "C24") (pin "2") (pinfunction "2_2") (pintype "passive"))
      (node (ref "C25") (pin "1") (pinfunction "1_1") (pintype "passive"))
      (node (ref "C32") (pin "2") (pinfunction "2_2") (pintype "passive"))
      (node (ref "C33") (pin "2") (pinfunction "2_2") (pintype "passive"))
      (node (ref "C6") (pin "2") (pinfunction "2_2") (pintype "passive"))
      (node (ref "C7") (pin "2") (pinfunction "2_2") (pintype "passive"))
      (node (ref "J2") (pin "1") (pinfunction "1_1") (pintype "passive"))
      (node (ref "J4") (pin "1") (pinfunction "1_1") (pintype "passive"))
      (node (ref "L5") (pin "2") (pinfunction "2_2") (pintype "passive"))
      (node (ref "R10") (pin "2") (pinfunction "2_2") (pintype "passive"))
      (node (ref "R13") (pin "2") (pinfunction "2_2") (pintype "passive"))
      (node (ref "R15") (pin "2") (pinfunction "2_2") (pintype "passive"))
      (node (ref "R19") (pin "1") (pinfunction "1_1") (pintype "passive"))
      (node (ref "R20") (pin "1") (pinfunction "1_1") (pintype "passive"))
      (node (ref "R23") (pin "2") (pinfunction "2_2") (pintype "passive"))
      (node (ref "R27") (pin "1") (pinfunction "1_1") (pintype "passive"))
      (node (ref "R4") (pin "2") (pinfunction "2_2") (pintype "passive"))
      (node (ref "U1") (pin "18") (pinfunction "VDD_18") (pintype "power_in"))
      (node (ref "U1") (pin "30") (pinfunction "VDD_30") (pintype "power_in"))
      (node (ref "U1") (pin "40") (pinfunction "VDD_40") (pintype "power_in"))
      (node (ref "U1") (pin "8") (pinfunction "VDD_8") (pintype "power_in"))
      (node (ref "U1") (pin "9") (pinfunction "VDDH_9") (pintype "power_in"))
      (node (ref "U2") (pin "8") (pinfunction "V+_8") (pintype "passive"))
      (node (ref "U3") (pin "8") (pinfunction "Vdd_8") (pintype "passive"))
      (node (ref "U4") (pin "8") (pinfunction "Vcc_8") (pintype "passive"))
      (node (ref "U5") (pin "8") (pinfunction "Vcc_8") (pintype "passive"))
    )
    (net (code "25") (name "5V") (class "Default")
      (node (ref "C18") (pin "2") (pinfunction "2_2") (pintype "passive"))
      (node (ref "C30") (pin "2") (pinfunction "2_2") (pintype "passive"))
      (node (ref "C31") (pin "2") (pinfunction "2_2") (pintype "passive"))
      (node (ref "FB1") (pin "2") (pinfunction "2_2") (pintype "passive"))
      (node (ref "K1") (pin "3") (pinfunction "3_3") (pintype "passive"))
      (node (ref "U1") (pin "10") (pinfunction "VBUS_10") (pintype "power_in"))
      (node (ref "U8") (pin "4") (pinfunction "EN_4") (pintype "passive"))
      (node (ref "U8") (pin "5") (pinfunction "Vin_5") (pintype "passive"))
      (node (ref "VD1") (pin "3") (pinfunction "3_3") (pintype "passive"))
    )
    (net (code "26") (name "GND") (class "Default")
      (node (ref "ANT1") (pin "G1") (pinfunction "G1_G1") (pintype "passive"))
      (node (ref "ANT1") (pin "G2") (pinfunction "GND_G2") (pintype "passive"))
      (node (ref "C1") (pin "2") (pinfunction "2_2") (pintype "passive"))
      (node (ref "C11") (pin "2") (pinfunction "2_2") (pintype "passive"))
      (node (ref "C12") (pin "1") (pinfunction "1_1") (pintype "passive"))
      (node (ref "C13") (pin "2") (pinfunction "2_2") (pintype "passive"))
      (node (ref "C14") (pin "1") (pinfunction "1_1") (pintype "passive"))
      (node (ref "C15") (pin "1") (pinfunction "1_1") (pintype "passive"))
      (node (ref "C16") (pin "1") (pinfunction "1_1") (pintype "passive"))
      (node (ref "C17") (pin "1") (pinfunction "1_1") (pintype "passive"))
      (node (ref "C18") (pin "1") (pinfunction "1_1") (pintype "passive"))
      (node (ref "C19") (pin "2") (pinfunction "2_2") (pintype "passive"))
      (node (ref "C2") (pin "1") (pinfunction "1_1") (pintype "passive"))
      (node (ref "C20") (pin "1") (pinfunction "1_1") (pintype "passive"))
      (node (ref "C21") (pin "1") (pinfunction "1_1") (pintype "passive"))
      (node (ref "C22") (pin "1") (pinfunction "1_1") (pintype "passive"))
      (node (ref "C23") (pin "1") (pinfunction "1_1") (pintype "passive"))
      (node (ref "C24") (pin "1") (pinfunction "1_1") (pintype "passive"))
      (node (ref "C25") (pin "2") (pinfunction "2_2") (pintype "passive"))
      (node (ref "C26") (pin "1") (pinfunction "1_1") (pintype "passive"))
      (node (ref "C27") (pin "1") (pinfunction "1_1") (pintype "passive"))
      (node (ref "C28") (pin "2") (pinfunction "2_2") (pintype "passive"))
      (node (ref "C29") (pin "1") (pinfunction "1_1") (pintype "passive"))
      (node (ref "C3") (pin "1") (pinfunction "1_1") (pintype "passive"))
      (node (ref "C30") (pin "1") (pinfunction "1_1") (pintype "passive"))
      (node (ref "C31") (pin "1") (pinfunction "1_1") (pintype "passive"))
      (node (ref "C33") (pin "1") (pinfunction "1_1") (pintype "passive"))
      (node (ref "C4") (pin "1") (pinfunction "1_1") (pintype "passive"))
      (node (ref "C5") (pin "2") (pinfunction "2_2") (pintype "passive"))
      (node (ref "C6") (pin "1") (pinfunction "1_1") (pintype "passive"))
      (node (ref "C7") (pin "1") (pinfunction "1_1") (pintype "passive"))
      (node (ref "C8") (pin "1") (pinfunction "1_1") (pintype "passive"))
      (node (ref "J3") (pin "3") (pinfunction "3_3") (pintype "passive"))
      (node (ref "J4") (pin "3") (pinfunction "3_3") (pintype "passive"))
      (node (ref "J4") (pin "5") (pinfunction "5_5") (pintype "passive"))
      (node (ref "J5") (pin "A1_B12") (pinfunction "GND_A1_B12") (pintype "passive"))
      (node (ref "J5") (pin "B1_A12") (pinfunction "GND_B1_A12") (pintype "passive"))
      (node (ref "J5") (pin "SH1") (pinfunction "SHELL_GND_SH1") (pintype "passive"))
      (node (ref "J5") (pin "SH2") (pinfunction "SHELL_GND_SH2") (pintype "passive"))
      (node (ref "J5") (pin "SH3") (pinfunction "SHELL_GND_SH3") (pintype "passive"))
      (node (ref "J5") (pin "SH4") (pinfunction "SHELL_GND_SH4") (pintype "passive"))
      (node (ref "K2") (pin "1") (pinfunction "1_1") (pintype "passive"))
      (node (ref "Q1") (pin "3") (pinfunction "S_3") (pintype "passive"))
      (node (ref "R11") (pin "1") (pinfunction "1_1") (pintype "passive"))
      (node (ref "R12") (pin "1") (pinfunction "1_1") (pintype "passive"))
      (node (ref "R2") (pin "1") (pinfunction "1_1") (pintype "passive"))
      (node (ref "R22") (pin "1") (pinfunction "1_1") (pintype "passive"))
      (node (ref "R24") (pin "1") (pinfunction "1_1") (pintype "passive"))
      (node (ref "R25") (pin "1") (pinfunction "1_1") (pintype "passive"))
      (node (ref "R26") (pin "1") (pinfunction "1_1") (pintype "passive"))
      (node (ref "R6") (pin "1") (pinfunction "1_1") (pintype "passive"))
      (node (ref "R9") (pin "1") (pinfunction "1_1") (pintype "passive"))
      (node (ref "U1") (pin "25") (pinfunction "VSS_PA_25") (pintype "power_in"))
      (node (ref "U1") (pin "37") (pinfunction "VSS_37") (pintype "power_in"))
      (node (ref "U1") (pin "41") (pinfunction "VSS_41") (pintype "power_in"))
      (node (ref "U2") (pin "4") (pinfunction "V-_4") (pintype "passive"))
      (node (ref "U3") (pin "3") (pinfunction "VIN-_3") (pintype "passive"))
      (node (ref "U3") (pin "4") (pinfunction "Vss_4") (pintype "passive"))
      (node (ref "U4") (pin "4") (pinfunction "Vss_4") (pintype "passive"))
      (node (ref "U5") (pin "5") (pinfunction "GND_5") (pintype "passive"))
      (node (ref "U6") (pin "3") (pinfunction "GND_3") (pintype "passive"))
      (node (ref "U7") (pin "2") (pinfunction "GND_2") (pintype "power_in"))
      (node (ref "U8") (pin "2") (pinfunction "MODE_2") (pintype "passive"))
      (node (ref "U8") (pin "6") (pinfunction "GND_6") (pintype "passive"))
      (node (ref "VD2") (pin "1") (pinfunction "K_1") (pintype "passive"))
      (node (ref "VD3") (pin "2") (pinfunction "2_2") (pintype "passive"))
      (node (ref "VD4") (pin "2") (pinfunction "2_2") (pintype "passive"))
      (node (ref "VD5") (pin "2") (pinfunction "2_2") (pintype "passive"))
      (node (ref "VD6") (pin "1") (pinfunction "K_1") (pintype "passive"))
    )
    (net (code "27") (name "Net-(ANT1-PadFEED)") (class "Default")
      (node (ref "ANT1") (pin "FEED") (pinfunction "FEED_FEED") (pintype "passive"))
      (node (ref "L4") (pin "2") (pinfunction "2_2") (pintype "passive"))
    )
    (net (code "28") (name "Net-(C10-Pad1)") (class "Default")
      (node (ref "C10") (pin "1") (pinfunction "1_1") (pintype "passive"))
      (node (ref "C9") (pin "1") (pinfunction "1_1") (pintype "passive"))
      (node (ref "R3") (pin "2") (pinfunction "2_2") (pintype "passive"))
    )
    (net (code "29") (name "Net-(C15-Pad2)") (class "Default")
      (node (ref "C15") (pin "2") (pinfunction "2_2") (pintype "passive"))
      (node (ref "L3") (pin "2") (pinfunction "2_2") (pintype "passive"))
      (node (ref "L4") (pin "1") (pinfunction "1_1") (pintype "passive"))
    )
    (net (code "30") (name "Net-(C28-Pad1)") (class "Default")
      (node (ref "C28") (pin "1") (pinfunction "1_1") (pintype "passive"))
      (node (ref "R18") (pin "2") (pinfunction "2_2") (pintype "passive"))
    )
    (net (code "31") (name "Net-(J4-Pad2)") (class "Default")
      (node (ref "J4") (pin "2") (pinfunction "2_2") (pintype "passive"))
      (node (ref "R14") (pin "1") (pinfunction "1_1") (pintype "passive"))
      (node (ref "VD5") (pin "1") (pinfunction "1_1") (pintype "passive"))
    )
    (net (code "32") (name "Net-(J4-Pad4)") (class "Default")
      (node (ref "J4") (pin "4") (pinfunction "4_4") (pintype "passive"))
      (node (ref "R17") (pin "1") (pinfunction "1_1") (pintype "passive"))
      (node (ref "VD4") (pin "1") (pinfunction "1_1") (pintype "passive"))
    )
    (net (code "33") (name "Net-(J4-Pad10)") (class "Default")
      (node (ref "J4") (pin "10") (pinfunction "10_10") (pintype "passive"))
      (node (ref "R21") (pin "1") (pinfunction "1_1") (pintype "passive"))
      (node (ref "VD3") (pin "1") (pinfunction "1_1") (pintype "passive"))
    )
    (net (code "34") (name "Net-(J5-CC1)") (class "Default")
      (node (ref "J5") (pin "A5") (pinfunction "CC1_A5") (pintype "passive"))
      (node (ref "R25") (pin "2") (pinfunction "2_2") (pintype "passive"))
    )
    (net (code "35") (name "Net-(J5-CC2)") (class "Default")
      (node (ref "J5") (pin "B5") (pinfunction "CC2_B5") (pintype "passive"))
      (node (ref "R26") (pin "2") (pinfunction "2_2") (pintype "passive"))
    )
    (net (code "36") (name "Net-(L1-Pad1)") (class "Default")
      (node (ref "L1") (pin "1") (pinfunction "1_1") (pintype "passive"))
      (node (ref "L2") (pin "2") (pinfunction "2_2") (pintype "passive"))
    )
    (net (code "37") (name "Net-(Q1-D)") (class "Default")
      (node (ref "K1") (pin "4") (pinfunction "4_4") (pintype "passive"))
      (node (ref "Q1") (pin "2") (pinfunction "D_2") (pintype "passive"))
      (node (ref "VD1") (pin "2") (pinfunction "2_2") (pintype "passive"))
    )
    (net (code "38") (name "Net-(Q1-G)") (class "Default")
      (node (ref "Q1") (pin "1") (pinfunction "G_1") (pintype "passive"))
      (node (ref "R1") (pin "2") (pinfunction "2_2") (pintype "passive"))
      (node (ref "R2") (pin "2") (pinfunction "2_2") (pintype "passive"))
    )
    (net (code "39") (name "Net-(U1-ANT)") (class "Default")
      (node (ref "C14") (pin "2") (pinfunction "2_2") (pintype "passive"))
      (node (ref "L3") (pin "1") (pinfunction "1_1") (pintype "passive"))
      (node (ref "U1") (pin "24") (pinfunction "ANT_24") (pintype "passive"))
    )
    (net (code "40") (name "Net-(U1-DCC)") (class "Default")
      (node (ref "L2") (pin "1") (pinfunction "1_1") (pintype "passive"))
      (node (ref "U1") (pin "39") (pinfunction "DCC_39") (pintype "passive"))
    )
    (net (code "41") (name "Net-(U1-DEC1)") (class "Default")
      (node (ref "C12") (pin "2") (pinfunction "2_2") (pintype "passive"))
      (node (ref "U1") (pin "1") (pinfunction "DEC1_1") (pintype "power_in"))
    )
    (net (code "42") (name "Net-(U1-DEC3)") (class "Default")
      (node (ref "C11") (pin "1") (pinfunction "1_1") (pintype "passive"))
      (node (ref "U1") (pin "27") (pinfunction "DEC3_27") (pintype "power_in"))
    )
    (net (code "43") (name "Net-(U1-DEC4)") (class "Default")
      (node (ref "C13") (pin "1") (pinfunction "1_1") (pintype "passive"))
      (node (ref "C2") (pin "2") (pinfunction "2_2") (pintype "passive"))
      (node (ref "C3") (pin "2") (pinfunction "2_2") (pintype "passive"))
      (node (ref "L1") (pin "2") (pinfunction "2_2") (pintype "passive"))
      (node (ref "U1") (pin "26") (pinfunction "DEC6_26") (pintype "power_in"))
      (node (ref "U1") (pin "38") (pinfunction "DEC4_38") (pintype "power_in"))
    )
    (net (code "44") (name "Net-(U1-DEC5)") (class "Default")
      (node (ref "C17") (pin "2") (pinfunction "2_2") (pintype "passive"))
      (node (ref "U1") (pin "21") (pinfunction "DEC5_21") (pintype "power_in"))
    )
    (net (code "45") (name "Net-(U1-DECUSB)") (class "Default")
      (node (ref "C22") (pin "2") (pinfunction "2_2") (pintype "passive"))
      (node (ref "U1") (pin "11") (pinfunction "DECUSB_11") (pintype "power_in"))
    )
    (net (code "46") (name "Net-(U1-P0.00{slash}XL1)") (class "Default")
      (node (ref "C4") (pin "2") (pinfunction "2_2") (pintype "passive"))
      (node (ref "U1") (pin "2") (pinfunction "P0.00/XL1_2") (pintype "passive"))
      (node (ref "X2") (pin "1") (pinfunction "inp_1") (pintype "passive"))
    )
    (net (code "47") (name "Net-(U1-P0.01{slash}XL2)") (class "Default")
      (node (ref "C8") (pin "2") (pinfunction "2_2") (pintype "passive"))
      (node (ref "U1") (pin "3") (pinfunction "P0.01/XL2_3") (pintype "passive"))
      (node (ref "X2") (pin "2") (pinfunction "out_2") (pintype "passive"))
    )
    (net (code "48") (name "Net-(U1-XC1)") (class "Default")
      (node (ref "C5") (pin "1") (pinfunction "1_1") (pintype "passive"))
      (node (ref "U1") (pin "28") (pinfunction "XC1_28") (pintype "passive"))
      (node (ref "X1") (pin "1") (pinfunction "inp_1") (pintype "passive"))
    )
    (net (code "49") (name "Net-(U1-XC2)") (class "Default")
      (node (ref "C1") (pin "1") (pinfunction "1_1") (pintype "passive"))
      (node (ref "U1") (pin "29") (pinfunction "XC2_29") (pintype "passive"))
      (node (ref "X1") (pin "3") (pinfunction "out_3") (pintype "passive"))
    )
    (net (code "50") (name "Net-(U2-IN1+)") (class "Default")
      (node (ref "J2") (pin "2") (pinfunction "2_2") (pintype "passive"))
      (node (ref "R11") (pin "2") (pinfunction "2_2") (pintype "passive"))
      (node (ref "U2") (pin "3") (pinfunction "IN1+_3") (pintype "passive"))
    )
    (net (code "51") (name "Net-(U2-IN1-)") (class "Default")
      (node (ref "R4") (pin "1") (pinfunction "1_1") (pintype "passive"))
      (node (ref "R5") (pin "1") (pinfunction "1_1") (pintype "passive"))
      (node (ref "R6") (pin "2") (pinfunction "2_2") (pintype "passive"))
      (node (ref "U2") (pin "2") (pinfunction "IN1-_2") (pintype "passive"))
    )
    (net (code "52") (name "Net-(U2-IN2+)") (class "Default")
      (node (ref "R10") (pin "1") (pinfunction "1_1") (pintype "passive"))
      (node (ref "R12") (pin "2") (pinfunction "2_2") (pintype "passive"))
      (node (ref "U2") (pin "5") (pinfunction "IN2+_5") (pintype "passive"))
    )
    (net (code "53") (name "Net-(U3-VIN+)") (class "Default")
      (node (ref "R7") (pin "2") (pinfunction "2_2") (pintype "passive"))
      (node (ref "TP4") (pin "1") (pinfunction "1_1") (pintype "passive"))
      (node (ref "U3") (pin "2") (pinfunction "VIN+_2") (pintype "passive"))
    )
    (net (code "54") (name "Net-(U4-OSCI)") (class "Default")
      (node (ref "C26") (pin "2") (pinfunction "2_2") (pintype "passive"))
      (node (ref "U4") (pin "1") (pinfunction "OSCI_1") (pintype "passive"))
      (node (ref "X3") (pin "2") (pinfunction "out_2") (pintype "passive"))
    )
    (net (code "55") (name "Net-(U4-OSCO)") (class "Default")
      (node (ref "C27") (pin "2") (pinfunction "2_2") (pintype "passive"))
      (node (ref "U4") (pin "2") (pinfunction "OSCO_2") (pintype "passive"))
      (node (ref "X3") (pin "1") (pinfunction "inp_1") (pintype "passive"))
    )
    (net (code "56") (name "Net-(U8-FB)") (class "Default")
      (node (ref "C32") (pin "1") (pinfunction "1_1") (pintype "passive"))
      (node (ref "R23") (pin "1") (pinfunction "1_1") (pintype "passive"))
      (node (ref "R24") (pin "2") (pinfunction "2_2") (pintype "passive"))
      (node (ref "U8") (pin "3") (pinfunction "FB_3") (pintype "passive"))
    )
    (net (code "57") (name "Net-(U8-SW)") (class "Default")
      (node (ref "L5") (pin "1") (pinfunction "1_1") (pintype "passive"))
      (node (ref "U8") (pin "1") (pinfunction "SW_1") (pintype "passive"))
    )
    (net (code "58") (name "Net-(VD2-A)") (class "Default")
      (node (ref "R8") (pin "2") (pinfunction "2_2") (pintype "passive"))
      (node (ref "VD2") (pin "2") (pinfunction "A_2") (pintype "passive"))
    )
    (net (code "59") (name "Net-(VD6-A)") (class "Default")
      (node (ref "R27") (pin "2") (pinfunction "2_2") (pintype "passive"))
      (node (ref "VD6") (pin "2") (pinfunction "A_2") (pintype "passive"))
    )
    (net (code "60") (name "VBUS") (class "Default")
      (node (ref "C29") (pin "2") (pinfunction "2_2") (pintype "passive"))
      (node (ref "FB1") (pin "1") (pinfunction "1_1") (pintype "passive"))
      (node (ref "J5") (pin "A4_B9") (pinfunction "VBUS_A4_B9") (pintype "passive"))
      (node (ref "J5") (pin "B4_A9") (pinfunction "VBUS_B4_A9") (pintype "passive"))
      (node (ref "U7") (pin "5") (pinfunction "VBUS_5") (pintype "power_in"))
    )
    (net (code "61") (name "unconnected-(J4-Pad6)") (class "Default")
      (node (ref "J4") (pin "6") (pinfunction "6_6") (pintype "passive+no_connect"))
    )
    (net (code "62") (name "unconnected-(J4-Pad7)") (class "Default")
      (node (ref "J4") (pin "7") (pinfunction "7_7") (pintype "passive+no_connect"))
    )
    (net (code "63") (name "unconnected-(J4-Pad8)") (class "Default")
      (node (ref "J4") (pin "8") (pinfunction "8_8") (pintype "passive+no_connect"))
    )
    (net (code "64") (name "unconnected-(J4-Pad9)") (class "Default")
      (node (ref "J4") (pin "9") (pinfunction "9_9") (pintype "passive+no_connect"))
    )
    (net (code "65") (name "unconnected-(J5-SBU1-PadA8)") (class "Default")
      (node (ref "J5") (pin "A8") (pinfunction "SBU1_A8") (pintype "passive+no_connect"))
    )
    (net (code "66") (name "unconnected-(J5-SBU2-PadB8)") (class "Default")
      (node (ref "J5") (pin "B8") (pinfunction "SBU2_B8") (pintype "passive+no_connect"))
    )
    (net (code "67") (name "unconnected-(U1-P0.02{slash}AIN0-Pad36)") (class "Default")
      (node (ref "U1") (pin "36") (pinfunction "P0.02/AIN0_36") (pintype "passive"))
    )
    (net (code "68") (name "unconnected-(U1-P0.03{slash}AIN1-Pad35)") (class "Default")
      (node (ref "U1") (pin "35") (pinfunction "P0.03/AIN1_35") (pintype "passive"))
    )
    (net (code "69") (name "unconnected-(U1-P0.16-Pad22)") (class "Default")
      (node (ref "U1") (pin "22") (pinfunction "P0.16_22") (pintype "passive"))
    )
    (net (code "70") (name "unconnected-(U1-P0.17-Pad23)") (class "Default")
      (node (ref "U1") (pin "23") (pinfunction "P0.17_23") (pintype "passive"))
    )
    (net (code "71") (name "unconnected-(U1-P0.20-Pad17)") (class "Default")
      (node (ref "U1") (pin "17") (pinfunction "P0.20_17") (pintype "passive"))
    )
    (net (code "72") (name "unconnected-(U4-NF-Pad3)") (class "Default")
      (node (ref "U4") (pin "3") (pinfunction "NF_3") (pintype "passive+no_connect"))
    )
    (net (code "73") (name "unconnected-(U4-OUT-Pad7)") (class "Default")
      (node (ref "U4") (pin "7") (pinfunction "OUT_7") (pintype "passive+no_connect"))
    )
  )
)
